# MPU6500.net
KiCad netlist of a schematic drawn in EasyEDA Pro
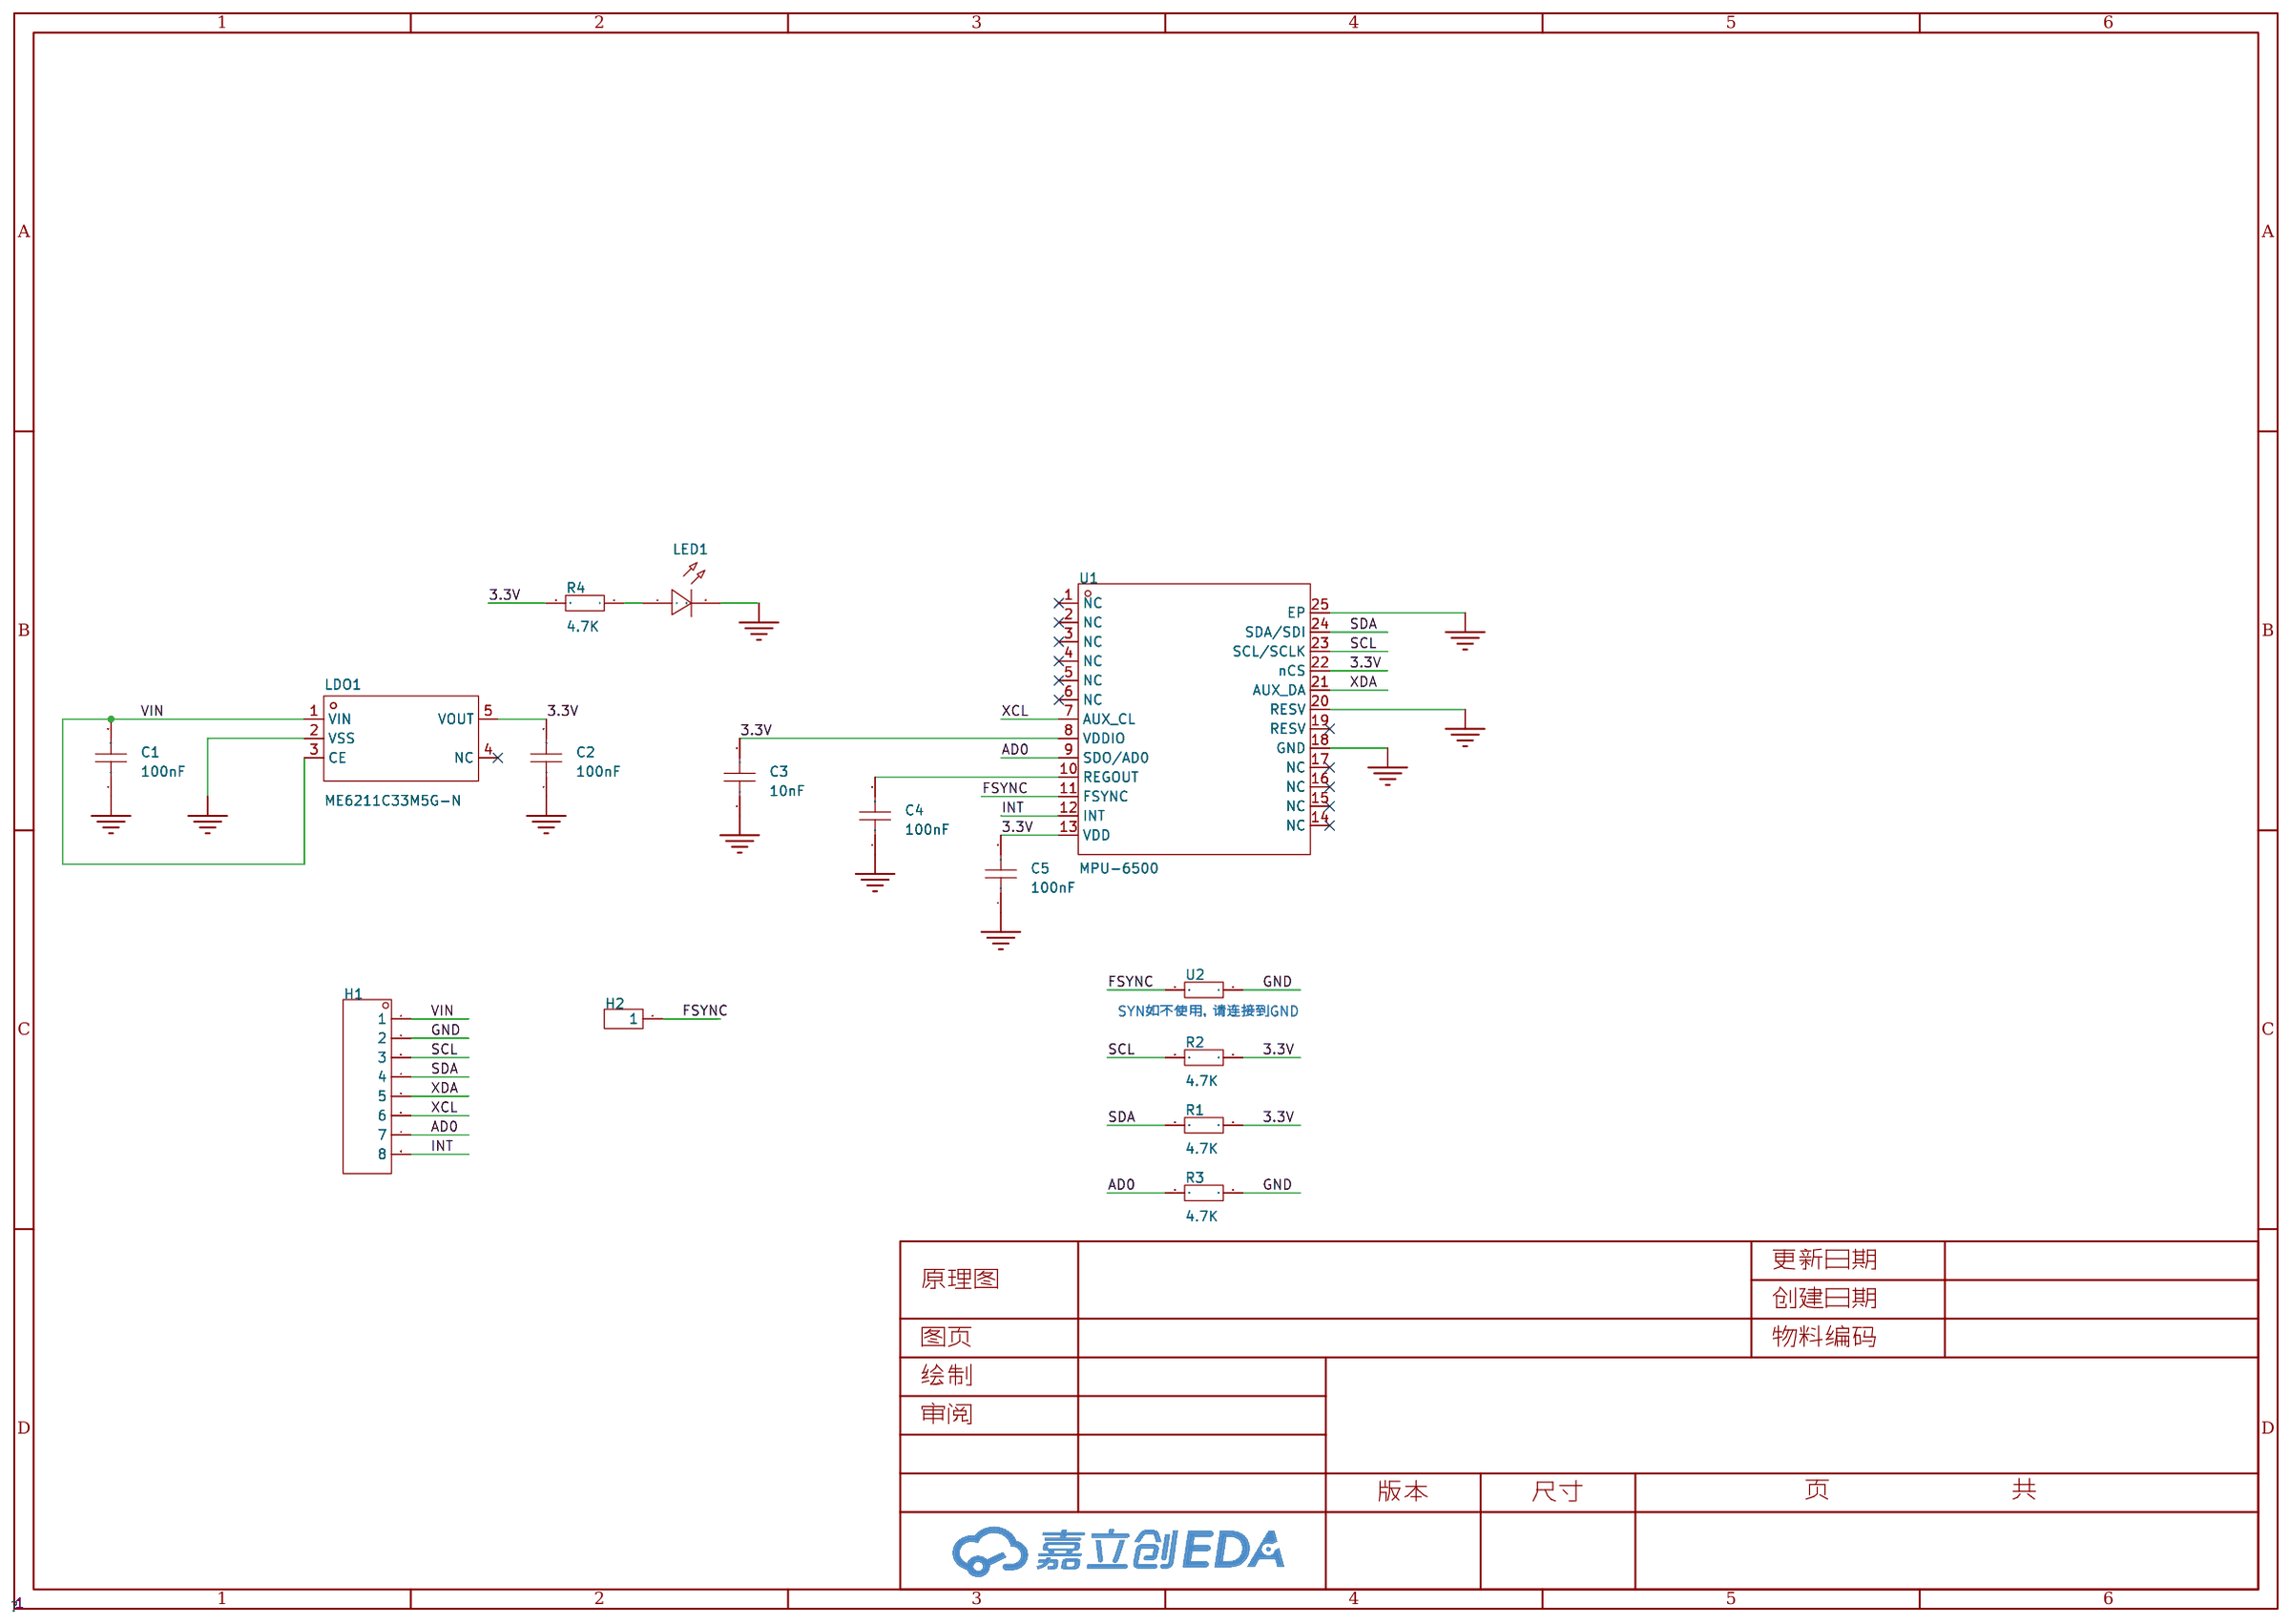
[diagram p0: schematic sheet]

(export (version "E")
  (design (tool "Eeschema 10.0.6"))
  (components
    (comp (ref "C1")
      (value "100nF")
      (footprint "easyedapro:C0603")
      (libsource (lib "easyedapro") (part "CapAcitance"))
    )
    (comp (ref "C2")
      (value "100nF")
      (footprint "easyedapro:C0603")
      (libsource (lib "easyedapro") (part "CapAcitance"))
    )
    (comp (ref "C3")
      (value "10nF")
      (footprint "easyedapro:C0603")
      (libsource (lib "easyedapro") (part "CapAcitance"))
    )
    (comp (ref "C4")
      (value "100nF")
      (footprint "easyedapro:C0603")
      (libsource (lib "easyedapro") (part "CapAcitance"))
    )
    (comp (ref "C5")
      (value "100nF")
      (footprint "easyedapro:C0603")
      (libsource (lib "easyedapro") (part "CapAcitance"))
    )
    (comp (ref "H1")
      (value "~")
      (footprint "easyedapro:HDR-TH_8P-P2.54-V-M")
      (libsource (lib "easyedapro") (part "Header-Male-2.54_1x8"))
    )
    (comp (ref "H2")
      (value "~")
      (footprint "easyedapro:HDR-TH_1P-V-M_XKB_X4611WV-01I-C28D40")
      (libsource (lib "easyedapro") (part "HDR_1x1"))
    )
    (comp (ref "LDO1")
      (value "ME6211C33M5G-N")
      (footprint "easyedapro:SOT-23-5_L3.0-W1.7-P0.95-LS2.8-BL")
      (description "输出类型:固定;最大输入电压:6V;输出电压:3.3V;最大输出电流:500mA;电源纹波抑制比(PSRR):70dB;输出极性:正极;")
      (fields (field (name "Manufacturer") "MICRONE(南京微盟)"))
      (libsource (lib "easyedapro") (part "ME6211C33M5G-N"))
    )
    (comp (ref "LED1")
      (value "~")
      (footprint "easyedapro:LED_0603_RED")
      (libsource (lib "easyedapro") (part "LED0603_R"))
    )
    (comp (ref "R1") (value "4.7K") (footprint "easyedapro:R0603") (libsource (lib "easyedapro") (part "电阻")))
    (comp (ref "R2") (value "4.7K") (footprint "easyedapro:R0603") (libsource (lib "easyedapro") (part "电阻")))
    (comp (ref "R3") (value "4.7K") (footprint "easyedapro:R0603") (libsource (lib "easyedapro") (part "电阻")))
    (comp (ref "R4") (value "4.7K") (footprint "easyedapro:R0603") (libsource (lib "easyedapro") (part "电阻")))
    (comp (ref "U1")
      (value "MPU-6500")
      (footprint "easyedapro:QFN-24_L3.0-W3.0-P0.40-BL-EP")
      (description "传感器类型:加速度计陀螺仪;")
      (fields (field (name "Manufacturer") "TDK InvenSense(应美盛)"))
      (libsource (lib "easyedapro") (part "MPU6500"))
    )
    (comp (ref "U2")
      (value "~")
      (footprint "easyedapro:R0603")
      (description "0603封装的跳线")
      (fields
        (field (name "Manufacturer Part") "0603WAF2200T5E")
        (field (name "Manufacturer") "UNI-ROYAL(厚声)")
      )
      (libsource (lib "easyedapro") (part "0603"))
    )
  )
  (nets
    (net (code "1") (name "/3.3V") (class "Default")
      (node (ref "C2") (pin "2") (pinfunction "2_2") (pintype "input"))
      (node (ref "C3") (pin "2") (pinfunction "2_2") (pintype "input"))
      (node (ref "C5") (pin "2") (pinfunction "2_2") (pintype "input"))
      (node (ref "LDO1") (pin "5") (pinfunction "VOUT_5") (pintype "input"))
      (node (ref "R1") (pin "1") (pinfunction "1_1") (pintype "input"))
      (node (ref "R2") (pin "1") (pinfunction "1_1") (pintype "input"))
      (node (ref "R4") (pin "2") (pinfunction "2_2") (pintype "input"))
      (node (ref "U1") (pin "13") (pinfunction "VDD_13") (pintype "unspecified"))
      (node (ref "U1") (pin "22") (pinfunction "nCS_22") (pintype "unspecified"))
      (node (ref "U1") (pin "8") (pinfunction "VDDIO_8") (pintype "unspecified"))
    )
    (net (code "2") (name "/AD0") (class "Default")
      (node (ref "H1") (pin "7") (pinfunction "7_7") (pintype "unspecified"))
      (node (ref "R3") (pin "2") (pinfunction "2_2") (pintype "input"))
      (node (ref "U1") (pin "9") (pinfunction "SDO/AD0_9") (pintype "unspecified"))
    )
    (net (code "3") (name "/FSYNC") (class "Default")
      (node (ref "H2") (pin "1") (pinfunction "1_1") (pintype "unspecified"))
      (node (ref "U1") (pin "11") (pinfunction "FSYNC_11") (pintype "unspecified"))
      (node (ref "U2") (pin "2") (pinfunction "2_2") (pintype "input"))
    )
    (net (code "4") (name "/INT") (class "Default")
      (node (ref "H1") (pin "8") (pinfunction "8_8") (pintype "unspecified"))
      (node (ref "U1") (pin "12") (pinfunction "INT_12") (pintype "unspecified"))
    )
    (net (code "5") (name "/SCL") (class "Default")
      (node (ref "H1") (pin "3") (pinfunction "3_3") (pintype "unspecified"))
      (node (ref "R2") (pin "2") (pinfunction "2_2") (pintype "input"))
      (node (ref "U1") (pin "23") (pinfunction "SCL/SCLK_23") (pintype "unspecified"))
    )
    (net (code "6") (name "/SDA") (class "Default")
      (node (ref "H1") (pin "4") (pinfunction "4_4") (pintype "unspecified"))
      (node (ref "R1") (pin "2") (pinfunction "2_2") (pintype "input"))
      (node (ref "U1") (pin "24") (pinfunction "SDA/SDI_24") (pintype "unspecified"))
    )
    (net (code "7") (name "/VIN") (class "Default")
      (node (ref "C1") (pin "2") (pinfunction "2_2") (pintype "input"))
      (node (ref "H1") (pin "1") (pinfunction "1_1") (pintype "unspecified"))
      (node (ref "LDO1") (pin "1") (pinfunction "VIN_1") (pintype "input"))
      (node (ref "LDO1") (pin "3") (pinfunction "CE_3") (pintype "input"))
    )
    (net (code "8") (name "/XCL") (class "Default")
      (node (ref "H1") (pin "6") (pinfunction "6_6") (pintype "unspecified"))
      (node (ref "U1") (pin "7") (pinfunction "AUX_CL_7") (pintype "unspecified"))
    )
    (net (code "9") (name "/XDA") (class "Default")
      (node (ref "H1") (pin "5") (pinfunction "5_5") (pintype "unspecified"))
      (node (ref "U1") (pin "21") (pinfunction "AUX_DA_21") (pintype "unspecified"))
    )
    (net (code "10") (name "GND") (class "Default")
      (node (ref "C1") (pin "1") (pinfunction "1_1") (pintype "input"))
      (node (ref "C2") (pin "1") (pinfunction "1_1") (pintype "input"))
      (node (ref "C3") (pin "1") (pinfunction "1_1") (pintype "input"))
      (node (ref "C4") (pin "1") (pinfunction "1_1") (pintype "input"))
      (node (ref "C5") (pin "1") (pinfunction "1_1") (pintype "input"))
      (node (ref "H1") (pin "2") (pinfunction "2_2") (pintype "unspecified"))
      (node (ref "LDO1") (pin "2") (pinfunction "VSS_2") (pintype "input"))
      (node (ref "LED1") (pin "2") (pinfunction "C_2") (pintype "input"))
      (node (ref "R3") (pin "1") (pinfunction "1_1") (pintype "input"))
      (node (ref "U1") (pin "18") (pinfunction "GND_18") (pintype "unspecified"))
      (node (ref "U1") (pin "20") (pinfunction "RESV_20") (pintype "unspecified"))
      (node (ref "U1") (pin "25") (pinfunction "EP_25") (pintype "unspecified"))
      (node (ref "U2") (pin "1") (pinfunction "1_1") (pintype "input"))
    )
    (net (code "11") (name "Net-(LED1-A)") (class "Default")
      (node (ref "LED1") (pin "1") (pinfunction "A_1") (pintype "input"))
      (node (ref "R4") (pin "1") (pinfunction "1_1") (pintype "input"))
    )
    (net (code "12") (name "Net-(U1-REGOUT)") (class "Default")
      (node (ref "C4") (pin "2") (pinfunction "2_2") (pintype "input"))
      (node (ref "U1") (pin "10") (pinfunction "REGOUT_10") (pintype "unspecified"))
    )
    (net (code "13") (name "unconnected-(LDO1-NC-Pad4)") (class "Default")
      (node (ref "LDO1") (pin "4") (pinfunction "NC_4") (pintype "input+no_connect"))
    )
    (net (code "14") (name "unconnected-(U1-NC-Pad1)") (class "Default")
      (node (ref "U1") (pin "1") (pinfunction "NC_1") (pintype "unspecified+no_connect"))
    )
    (net (code "15") (name "unconnected-(U1-NC-Pad2)") (class "Default")
      (node (ref "U1") (pin "2") (pinfunction "NC_2") (pintype "unspecified+no_connect"))
    )
    (net (code "16") (name "unconnected-(U1-NC-Pad3)") (class "Default")
      (node (ref "U1") (pin "3") (pinfunction "NC_3") (pintype "unspecified+no_connect"))
    )
    (net (code "17") (name "unconnected-(U1-NC-Pad4)") (class "Default")
      (node (ref "U1") (pin "4") (pinfunction "NC_4") (pintype "unspecified+no_connect"))
    )
    (net (code "18") (name "unconnected-(U1-NC-Pad5)") (class "Default")
      (node (ref "U1") (pin "5") (pinfunction "NC_5") (pintype "unspecified+no_connect"))
    )
    (net (code "19") (name "unconnected-(U1-NC-Pad6)") (class "Default")
      (node (ref "U1") (pin "6") (pinfunction "NC_6") (pintype "unspecified+no_connect"))
    )
    (net (code "20") (name "unconnected-(U1-NC-Pad14)") (class "Default")
      (node (ref "U1") (pin "14") (pinfunction "NC_14") (pintype "unspecified+no_connect"))
    )
    (net (code "21") (name "unconnected-(U1-NC-Pad15)") (class "Default")
      (node (ref "U1") (pin "15") (pinfunction "NC_15") (pintype "unspecified+no_connect"))
    )
    (net (code "22") (name "unconnected-(U1-NC-Pad16)") (class "Default")
      (node (ref "U1") (pin "16") (pinfunction "NC_16") (pintype "unspecified+no_connect"))
    )
    (net (code "23") (name "unconnected-(U1-NC-Pad17)") (class "Default")
      (node (ref "U1") (pin "17") (pinfunction "NC_17") (pintype "unspecified+no_connect"))
    )
    (net (code "24") (name "unconnected-(U1-RESV-Pad19)") (class "Default")
      (node (ref "U1") (pin "19") (pinfunction "RESV_19") (pintype "unspecified+no_connect"))
    )
  )
)
